# SilentStepStick_v12.net
KiCad netlist of a schematic drawn in EAGLE
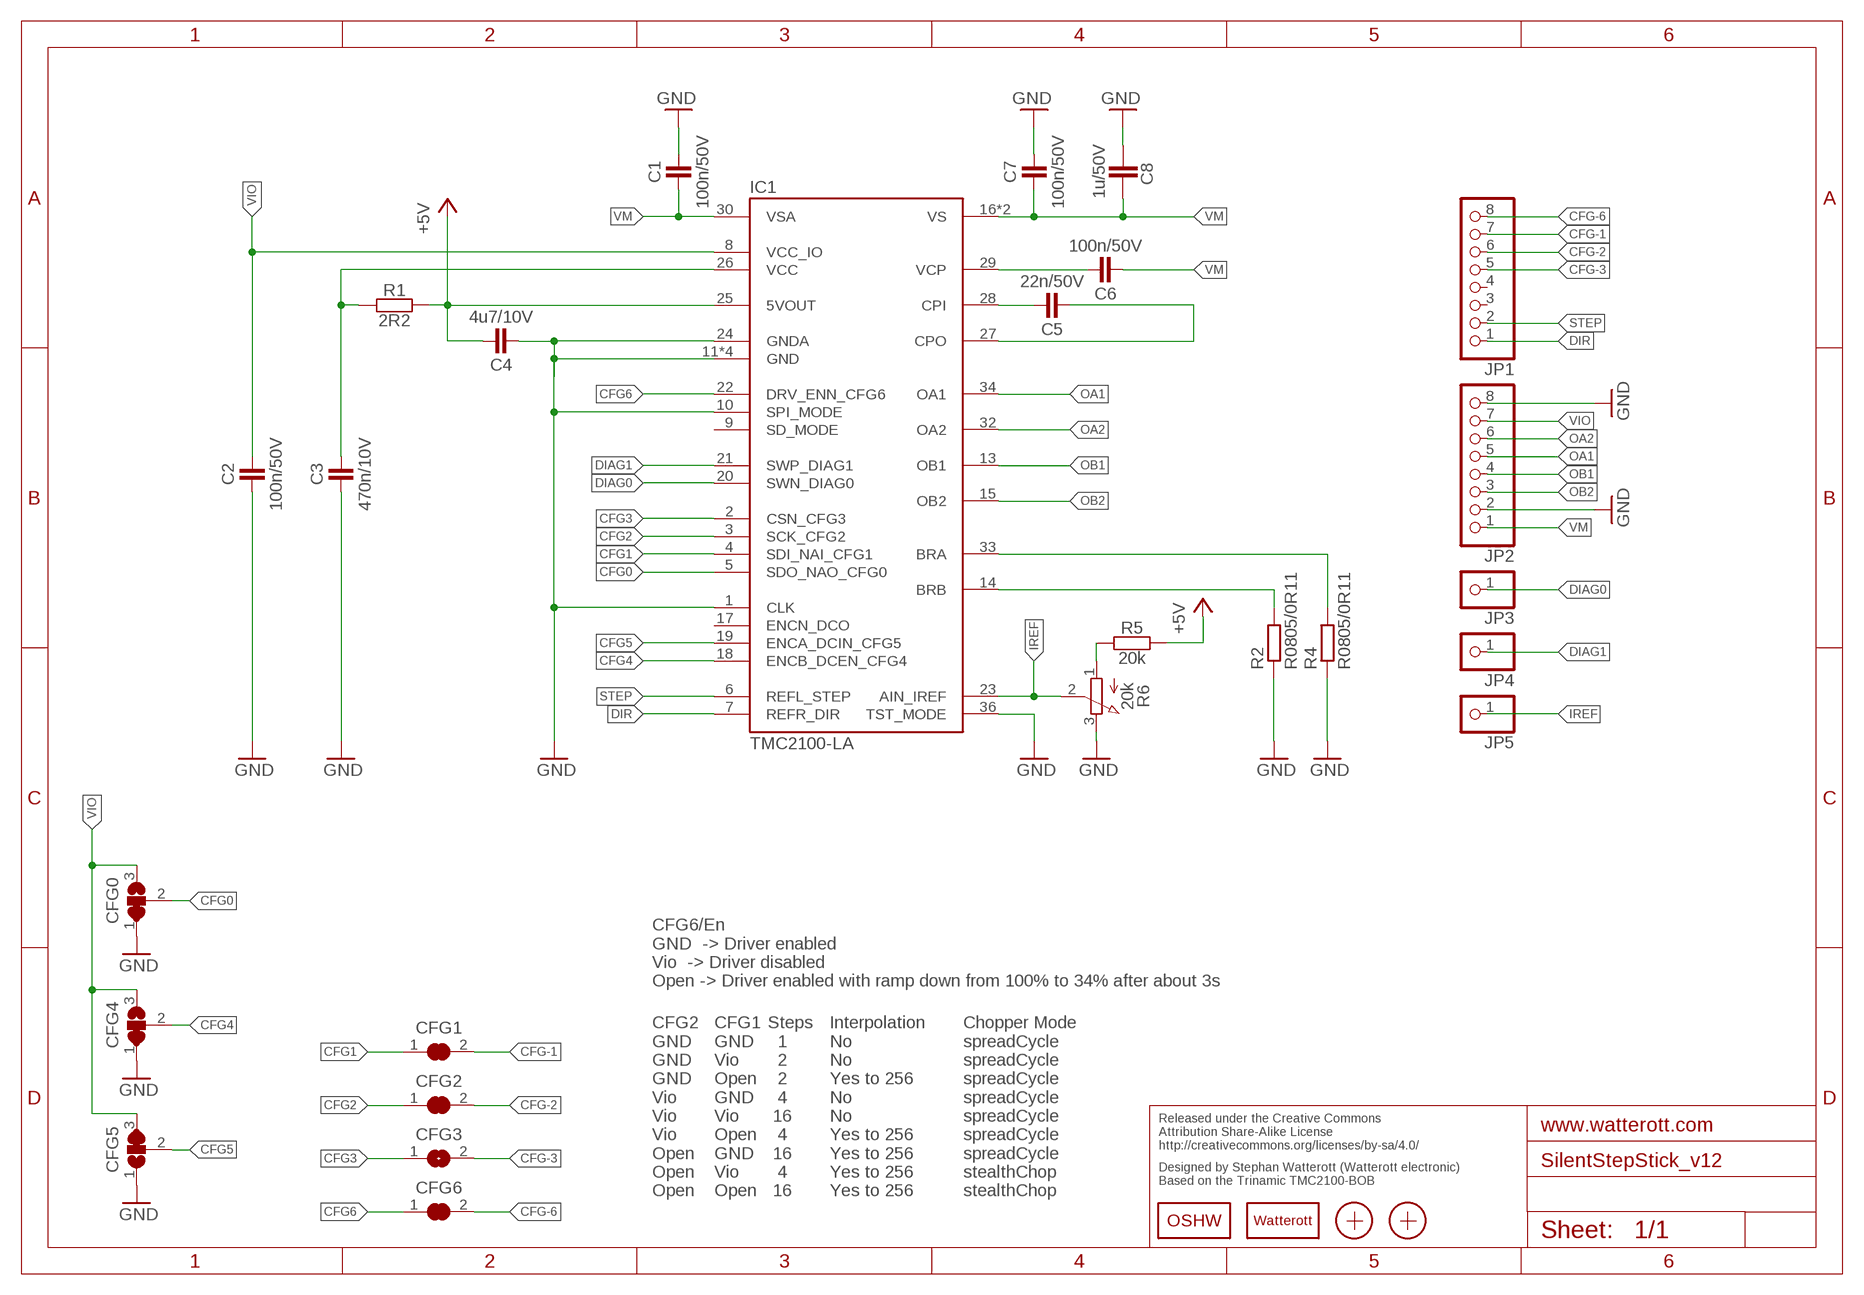
[diagram p0: schematic, sheet 1]

(export (version "E")
  (design (tool "Eeschema 10.0.6"))
  (components
    (comp (ref "C1")
      (value "100n/50V")
      (footprint "eagle-import:C0402")
      (libsource (lib "eagle-import") (part "CAPACITOR-0402"))
    )
    (comp (ref "C2")
      (value "100n/50V")
      (footprint "eagle-import:C0402")
      (libsource (lib "eagle-import") (part "CAPACITOR-0402"))
    )
    (comp (ref "C3")
      (value "470n/10V")
      (footprint "eagle-import:C0402")
      (libsource (lib "eagle-import") (part "CAPACITOR-0402"))
    )
    (comp (ref "C4")
      (value "4u7/10V")
      (footprint "eagle-import:C0402")
      (libsource (lib "eagle-import") (part "CAPACITOR-0402"))
    )
    (comp (ref "C5")
      (value "22n/50V")
      (footprint "eagle-import:C0402")
      (libsource (lib "eagle-import") (part "CAPACITOR-0402"))
    )
    (comp (ref "C6")
      (value "100n/50V")
      (footprint "eagle-import:C0402")
      (libsource (lib "eagle-import") (part "CAPACITOR-0402"))
    )
    (comp (ref "C7")
      (value "100n/50V")
      (footprint "eagle-import:C0402")
      (libsource (lib "eagle-import") (part "CAPACITOR-0402"))
    )
    (comp (ref "C8")
      (value "1u/50V")
      (footprint "eagle-import:C0603")
      (libsource (lib "eagle-import") (part "C-EUC0603"))
    )
    (comp (ref "CFG0")
      (value "JUMPER3-0201")
      (footprint "eagle-import:JUMPER3-0201")
      (libsource (lib "eagle-import") (part "JUMPER3-0201"))
    )
    (comp (ref "CFG1")
      (value "JUMPER2-0201")
      (footprint "eagle-import:JUMPER2-0201")
      (libsource (lib "eagle-import") (part "JUMPER2-0201"))
    )
    (comp (ref "CFG2")
      (value "JUMPER2-0201")
      (footprint "eagle-import:JUMPER2-0201")
      (libsource (lib "eagle-import") (part "JUMPER2-0201"))
    )
    (comp (ref "CFG3")
      (value "JUMPER2-0201")
      (footprint "eagle-import:JUMPER2-0201")
      (libsource (lib "eagle-import") (part "JUMPER2-0201"))
    )
    (comp (ref "CFG4")
      (value "JUMPER3-0201")
      (footprint "eagle-import:JUMPER3-0201")
      (libsource (lib "eagle-import") (part "JUMPER3-0201"))
    )
    (comp (ref "CFG5")
      (value "JUMPER3-0201")
      (footprint "eagle-import:JUMPER3-0201")
      (libsource (lib "eagle-import") (part "JUMPER3-0201"))
    )
    (comp (ref "CFG6")
      (value "JUMPER2-0201")
      (footprint "eagle-import:JUMPER2-0201")
      (libsource (lib "eagle-import") (part "JUMPER2-0201"))
    )
    (comp (ref "IC1")
      (value "TMC2100-LA")
      (footprint "eagle-import:QFN36-PAD")
      (libsource (lib "eagle-import") (part "TMC2100-LA"))
    )
    (comp (ref "JP1")
      (value "PINHD-1X08_2.54-S")
      (footprint "eagle-import:1X08-S")
      (libsource (lib "eagle-import") (part "PINHD-1X08_2.54-S"))
    )
    (comp (ref "JP2")
      (value "PINHD-1X08_2.54-S")
      (footprint "eagle-import:1X08-S")
      (libsource (lib "eagle-import") (part "PINHD-1X08_2.54-S"))
    )
    (comp (ref "JP3")
      (value "PINHD-1X1")
      (footprint "eagle-import:1X01")
      (libsource (lib "eagle-import") (part "PINHD-1X1"))
    )
    (comp (ref "JP4")
      (value "PINHD-1X1")
      (footprint "eagle-import:1X01")
      (libsource (lib "eagle-import") (part "PINHD-1X1"))
    )
    (comp (ref "JP5")
      (value "PINHD-1X1")
      (footprint "eagle-import:1X01")
      (libsource (lib "eagle-import") (part "PINHD-1X1"))
    )
    (comp (ref "LOGO1")
      (value "OSHW_LOGOX0070")
      (footprint "eagle-import:OSHW_6X70")
      (libsource (lib "eagle-import") (part "OSHW_LOGOX0070"))
    )
    (comp (ref "LOGO2")
      (value "LOGO-S_PLACE_M")
      (footprint "eagle-import:SPARK_TPLACE_M")
      (libsource (lib "eagle-import") (part "LOGO-S_PLACE_M"))
    )
    (comp (ref "R1")
      (value "2R2")
      (footprint "eagle-import:C0402")
      (libsource (lib "eagle-import") (part "RESISTOR-0402"))
    )
    (comp (ref "R2")
      (value "R0805/0R11")
      (footprint "eagle-import:M0805")
      (libsource (lib "eagle-import") (part "R-EU_M0805"))
    )
    (comp (ref "R4")
      (value "R0805/0R11")
      (footprint "eagle-import:M0805")
      (libsource (lib "eagle-import") (part "R-EU_M0805"))
    )
    (comp (ref "R5")
      (value "20k")
      (footprint "eagle-import:C0402")
      (libsource (lib "eagle-import") (part "RESISTOR-0402"))
    )
    (comp (ref "R6")
      (value "20k")
      (footprint "eagle-import:POT_EVM3R")
      (libsource (lib "eagle-import") (part "POTEVM3R"))
    )
    (comp (ref "X1")
      (value "PASSER-07")
      (footprint "eagle-import:PASSER_07MM")
      (libsource (lib "eagle-import") (part "PASSER-07"))
    )
    (comp (ref "X2")
      (value "PASSER-07")
      (footprint "eagle-import:PASSER_07MM")
      (libsource (lib "eagle-import") (part "PASSER-07"))
    )
  )
  (nets
    (net (code "1") (name "+5V") (class "Default")
      (node (ref "C4") (pin "2") (pinfunction "2_2") (pintype "passive"))
      (node (ref "IC1") (pin "25") (pinfunction "5VOUT_25") (pintype "power_in"))
      (node (ref "R1") (pin "2") (pinfunction "2_2") (pintype "passive"))
      (node (ref "R5") (pin "2") (pinfunction "2_2") (pintype "passive"))
    )
    (net (code "2") (name "CFG-1") (class "Default")
      (node (ref "CFG1") (pin "2") (pinfunction "2_2") (pintype "passive"))
      (node (ref "JP1") (pin "7") (pinfunction "7_7") (pintype "passive"))
    )
    (net (code "3") (name "CFG-2") (class "Default")
      (node (ref "CFG2") (pin "2") (pinfunction "2_2") (pintype "passive"))
      (node (ref "JP1") (pin "6") (pinfunction "6_6") (pintype "passive"))
    )
    (net (code "4") (name "CFG-3") (class "Default")
      (node (ref "CFG3") (pin "2") (pinfunction "2_2") (pintype "passive"))
      (node (ref "JP1") (pin "5") (pinfunction "5_5") (pintype "passive"))
    )
    (net (code "5") (name "CFG-6") (class "Default")
      (node (ref "CFG6") (pin "2") (pinfunction "2_2") (pintype "passive"))
      (node (ref "JP1") (pin "8") (pinfunction "8_8") (pintype "passive"))
    )
    (net (code "6") (name "CFG0") (class "Default")
      (node (ref "CFG0") (pin "2") (pinfunction "2_2") (pintype "passive"))
      (node (ref "IC1") (pin "5") (pinfunction "SDO_NAO_CFG0_5") (pintype "bidirectional"))
    )
    (net (code "7") (name "CFG1") (class "Default")
      (node (ref "CFG1") (pin "1") (pinfunction "1_1") (pintype "passive"))
      (node (ref "IC1") (pin "4") (pinfunction "SDI_NAI_CFG1_4") (pintype "bidirectional"))
    )
    (net (code "8") (name "CFG2") (class "Default")
      (node (ref "CFG2") (pin "1") (pinfunction "1_1") (pintype "passive"))
      (node (ref "IC1") (pin "3") (pinfunction "SCK_CFG2_3") (pintype "bidirectional"))
    )
    (net (code "9") (name "CFG3") (class "Default")
      (node (ref "CFG3") (pin "1") (pinfunction "1_1") (pintype "passive"))
      (node (ref "IC1") (pin "2") (pinfunction "CSN_CFG3_2") (pintype "bidirectional"))
    )
    (net (code "10") (name "CFG4") (class "Default")
      (node (ref "CFG4") (pin "2") (pinfunction "2_2") (pintype "passive"))
      (node (ref "IC1") (pin "18") (pinfunction "ENCB_DCEN_CFG4_18") (pintype "bidirectional"))
    )
    (net (code "11") (name "CFG5") (class "Default")
      (node (ref "CFG5") (pin "2") (pinfunction "2_2") (pintype "passive"))
      (node (ref "IC1") (pin "19") (pinfunction "ENCA_DCIN_CFG5_19") (pintype "bidirectional"))
    )
    (net (code "12") (name "CFG6") (class "Default")
      (node (ref "CFG6") (pin "1") (pinfunction "1_1") (pintype "passive"))
      (node (ref "IC1") (pin "22") (pinfunction "DRV_ENN_CFG6_22") (pintype "bidirectional"))
    )
    (net (code "13") (name "DIAG0") (class "Default")
      (node (ref "IC1") (pin "20") (pinfunction "SWN_DIAG0_20") (pintype "bidirectional"))
      (node (ref "JP3") (pin "1") (pinfunction "1_1") (pintype "passive"))
    )
    (net (code "14") (name "DIAG1") (class "Default")
      (node (ref "IC1") (pin "21") (pinfunction "SWP_DIAG1_21") (pintype "bidirectional"))
      (node (ref "JP4") (pin "1") (pinfunction "1_1") (pintype "passive"))
    )
    (net (code "15") (name "DIR") (class "Default")
      (node (ref "IC1") (pin "7") (pinfunction "REFR_DIR_7") (pintype "bidirectional"))
      (node (ref "JP1") (pin "1") (pinfunction "1_1") (pintype "passive"))
    )
    (net (code "16") (name "GND") (class "Default")
      (node (ref "C1") (pin "2") (pinfunction "2_2") (pintype "passive"))
      (node (ref "C2") (pin "1") (pinfunction "1_1") (pintype "passive"))
      (node (ref "C3") (pin "1") (pinfunction "1_1") (pintype "passive"))
      (node (ref "C4") (pin "1") (pinfunction "1_1") (pintype "passive"))
      (node (ref "C7") (pin "2") (pinfunction "2_2") (pintype "passive"))
      (node (ref "C8") (pin "2") (pinfunction "2_2") (pintype "passive"))
      (node (ref "CFG0") (pin "1") (pinfunction "1_1") (pintype "passive"))
      (node (ref "CFG4") (pin "1") (pinfunction "1_1") (pintype "passive"))
      (node (ref "CFG5") (pin "1") (pinfunction "1_1") (pintype "passive"))
      (node (ref "IC1") (pin "1") (pinfunction "CLK_1") (pintype "bidirectional"))
      (node (ref "IC1") (pin "10") (pinfunction "SPI_MODE_10") (pintype "bidirectional"))
      (node (ref "IC1") (pin "11") (pinfunction "GND_11") (pintype "power_in"))
      (node (ref "IC1") (pin "12") (pinfunction "GND_12") (pintype "power_in"))
      (node (ref "IC1") (pin "24") (pinfunction "GNDA_24") (pintype "power_in"))
      (node (ref "IC1") (pin "35") (pinfunction "GND_35") (pintype "power_in"))
      (node (ref "IC1") (pin "36") (pinfunction "TST_MODE_36") (pintype "bidirectional"))
      (node (ref "IC1") (pin "TP") (pinfunction "GND_TP") (pintype "power_in"))
      (node (ref "JP2") (pin "2") (pinfunction "2_2") (pintype "passive"))
      (node (ref "JP2") (pin "8") (pinfunction "8_8") (pintype "passive"))
      (node (ref "R2") (pin "1") (pinfunction "1_1") (pintype "passive"))
      (node (ref "R4") (pin "1") (pinfunction "1_1") (pintype "passive"))
      (node (ref "R6") (pin "3") (pinfunction "E_3") (pintype "passive"))
    )
    (net (code "17") (name "IREF") (class "Default")
      (node (ref "IC1") (pin "23") (pinfunction "AIN_IREF_23") (pintype "passive"))
      (node (ref "JP5") (pin "1") (pinfunction "1_1") (pintype "passive"))
      (node (ref "R6") (pin "2") (pinfunction "S_2") (pintype "passive"))
    )
    (net (code "18") (name "Net-(IC1-BRA)") (class "Default")
      (node (ref "IC1") (pin "33") (pinfunction "BRA_33") (pintype "output"))
      (node (ref "R4") (pin "2") (pinfunction "2_2") (pintype "passive"))
    )
    (net (code "19") (name "Net-(IC1-BRB)") (class "Default")
      (node (ref "IC1") (pin "14") (pinfunction "BRB_14") (pintype "output"))
      (node (ref "R2") (pin "2") (pinfunction "2_2") (pintype "passive"))
    )
    (net (code "20") (name "Net-(IC1-CPI)") (class "Default")
      (node (ref "C5") (pin "2") (pinfunction "2_2") (pintype "passive"))
      (node (ref "IC1") (pin "28") (pinfunction "CPI_28") (pintype "passive"))
    )
    (net (code "21") (name "Net-(IC1-CPO)") (class "Default")
      (node (ref "C5") (pin "1") (pinfunction "1_1") (pintype "passive"))
      (node (ref "IC1") (pin "27") (pinfunction "CPO_27") (pintype "passive"))
    )
    (net (code "22") (name "Net-(IC1-VCC)") (class "Default")
      (node (ref "C3") (pin "2") (pinfunction "2_2") (pintype "passive"))
      (node (ref "IC1") (pin "26") (pinfunction "VCC_26") (pintype "power_in"))
      (node (ref "R1") (pin "1") (pinfunction "1_1") (pintype "passive"))
    )
    (net (code "23") (name "Net-(IC1-VCP)") (class "Default")
      (node (ref "C6") (pin "2") (pinfunction "2_2") (pintype "passive"))
      (node (ref "IC1") (pin "29") (pinfunction "VCP_29") (pintype "passive"))
    )
    (net (code "24") (name "Net-(R6-A)") (class "Default")
      (node (ref "R5") (pin "1") (pinfunction "1_1") (pintype "passive"))
      (node (ref "R6") (pin "1") (pinfunction "A_1") (pintype "passive"))
    )
    (net (code "25") (name "OA1") (class "Default")
      (node (ref "IC1") (pin "34") (pinfunction "OA1_34") (pintype "output"))
      (node (ref "JP2") (pin "5") (pinfunction "5_5") (pintype "passive"))
    )
    (net (code "26") (name "OA2") (class "Default")
      (node (ref "IC1") (pin "32") (pinfunction "OA2_32") (pintype "output"))
      (node (ref "JP2") (pin "6") (pinfunction "6_6") (pintype "passive"))
    )
    (net (code "27") (name "OB1") (class "Default")
      (node (ref "IC1") (pin "13") (pinfunction "OB1_13") (pintype "output"))
      (node (ref "JP2") (pin "4") (pinfunction "4_4") (pintype "passive"))
    )
    (net (code "28") (name "OB2") (class "Default")
      (node (ref "IC1") (pin "15") (pinfunction "OB2_15") (pintype "output"))
      (node (ref "JP2") (pin "3") (pinfunction "3_3") (pintype "passive"))
    )
    (net (code "29") (name "STEP") (class "Default")
      (node (ref "IC1") (pin "6") (pinfunction "REFL_STEP_6") (pintype "bidirectional"))
      (node (ref "JP1") (pin "2") (pinfunction "2_2") (pintype "passive"))
    )
    (net (code "30") (name "VIO") (class "Default")
      (node (ref "C2") (pin "2") (pinfunction "2_2") (pintype "passive"))
      (node (ref "CFG0") (pin "3") (pinfunction "3_3") (pintype "passive"))
      (node (ref "CFG4") (pin "3") (pinfunction "3_3") (pintype "passive"))
      (node (ref "CFG5") (pin "3") (pinfunction "3_3") (pintype "passive"))
      (node (ref "IC1") (pin "8") (pinfunction "VCC_IO_8") (pintype "power_in"))
      (node (ref "JP2") (pin "7") (pinfunction "7_7") (pintype "passive"))
    )
    (net (code "31") (name "VM") (class "Default")
      (node (ref "C1") (pin "1") (pinfunction "1_1") (pintype "passive"))
      (node (ref "C6") (pin "1") (pinfunction "1_1") (pintype "passive"))
      (node (ref "C7") (pin "1") (pinfunction "1_1") (pintype "passive"))
      (node (ref "C8") (pin "1") (pinfunction "1_1") (pintype "passive"))
      (node (ref "IC1") (pin "16") (pinfunction "VS_16") (pintype "power_in"))
      (node (ref "IC1") (pin "30") (pinfunction "VSA_30") (pintype "power_in"))
      (node (ref "IC1") (pin "31") (pinfunction "VS_31") (pintype "power_in"))
      (node (ref "JP2") (pin "1") (pinfunction "1_1") (pintype "passive"))
    )
    (net (code "32") (name "unconnected-(IC1-ENCN_DCO-Pad17)") (class "Default")
      (node (ref "IC1") (pin "17") (pinfunction "ENCN_DCO_17") (pintype "bidirectional"))
    )
    (net (code "33") (name "unconnected-(IC1-SD_MODE-Pad9)") (class "Default")
      (node (ref "IC1") (pin "9") (pinfunction "SD_MODE_9") (pintype "bidirectional"))
    )
    (net (code "34") (name "unconnected-(JP1-Pad3)") (class "Default")
      (node (ref "JP1") (pin "3") (pinfunction "3_3") (pintype "passive"))
    )
    (net (code "35") (name "unconnected-(JP1-Pad4)") (class "Default")
      (node (ref "JP1") (pin "4") (pinfunction "4_4") (pintype "passive"))
    )
  )
)
